# board.net
KiCad netlist of a schematic drawn in EAGLE
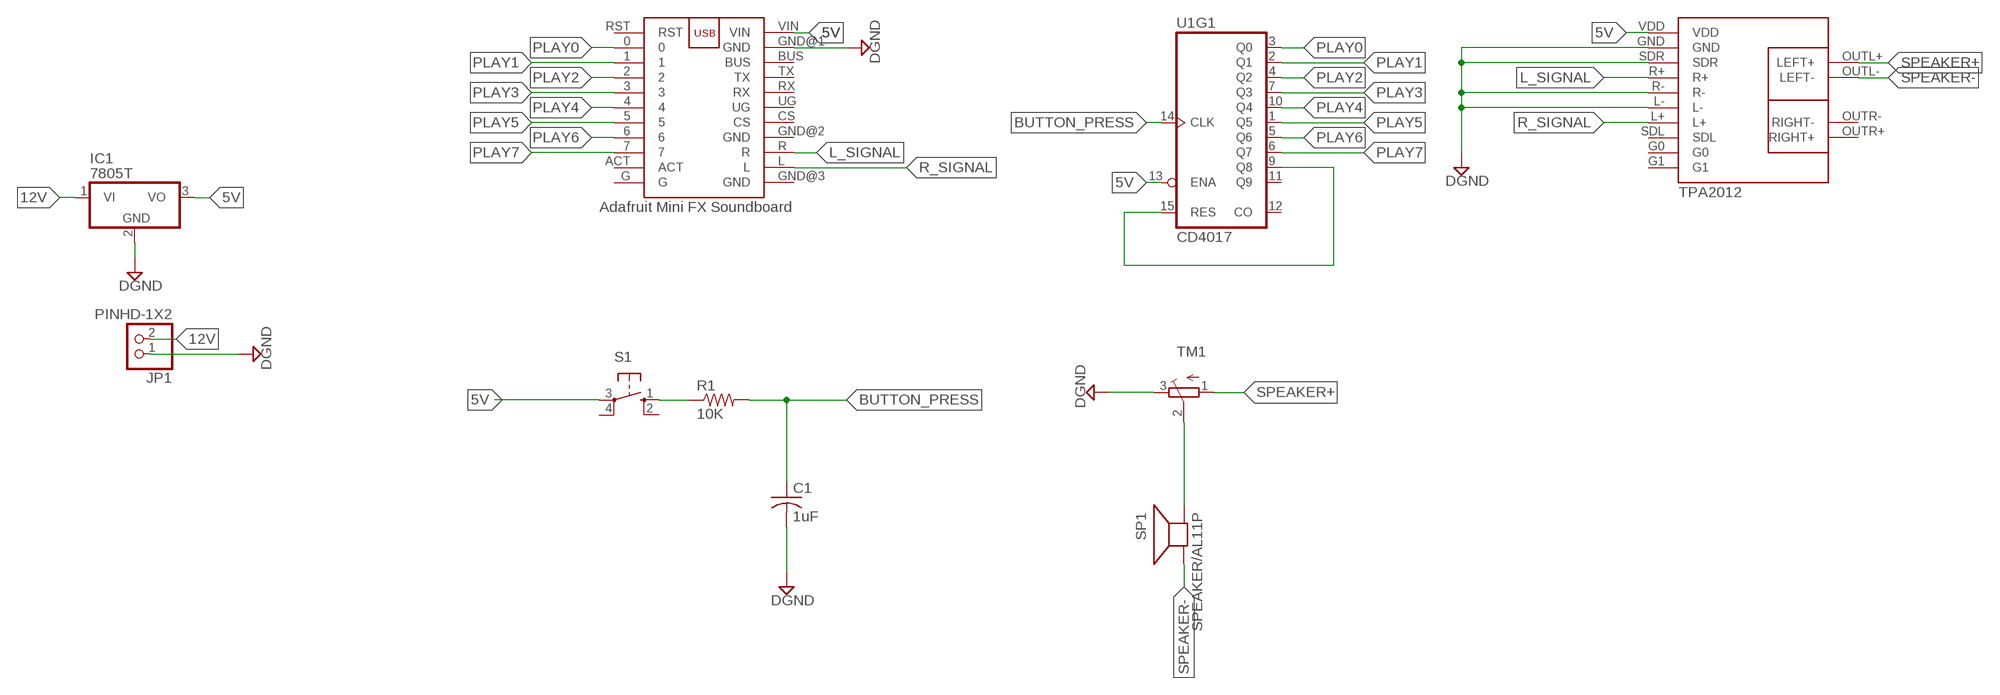
[diagram p0: schematic, sheet 1]

(export (version "E")
  (design (tool "Eeschema 10.0.6"))
  (components
    (comp (ref "C1")
      (value "1uF")
      (footprint "eagle-import:C025-050X050")
      (libsource (lib "eagle-import") (part "C-US025-050X050"))
    )
    (comp (ref "IC1")
      (value "7805T")
      (footprint "eagle-import:TO220H")
      (libsource (lib "eagle-import") (part "78T05"))
    )
    (comp (ref "JP1")
      (value "PINHD-1X2")
      (footprint "eagle-import:1X02")
      (libsource (lib "eagle-import") (part "PINHD-1X2"))
    )
    (comp (ref "R1")
      (value "10K")
      (footprint "eagle-import:0204_5")
      (libsource (lib "eagle-import") (part "R-US_0204/5"))
    )
    (comp (ref "S1")
      (value "10-XX")
      (footprint "eagle-import:B3F-10XX")
      (fields (field (name "MPN") "B3F-1000"))
      (libsource (lib "eagle-import") (part "10-XX"))
    )
    (comp (ref "SP1")
      (value "SPEAKER/AL11P")
      (footprint "eagle-import:AL11P")
      (libsource (lib "eagle-import") (part "SPEAKER/AL11P"))
    )
    (comp (ref "TM1")
      (value "TRIMPOT3386")
      (footprint "eagle-import:TRIM-3386")
      (libsource (lib "eagle-import") (part "TRIMPOT3386"))
    )
    (comp (ref "U$1")
      (value "TPA2012")
      (footprint "eagle-import:TPA2012")
      (libsource (lib "eagle-import") (part "TPA2012"))
    )
    (comp (ref "U$2")
      (value "ADAFRUIT_AUDIO_FX_MINI_SOUNDBOARD")
      (footprint "eagle-import:ADAFRUIT_AUDIO_FX_MINI_SOUNDBOARD")
      (libsource (lib "eagle-import") (part "ADAFRUIT_AUDIO_FX_MINI_SOUNDBOARD"))
    )
    (comp (ref "U1")
      (value "CD4017")
      (footprint "eagle-import:DIP16")
      (libsource (lib "eagle-import") (part "CD4017"))
    )
  )
  (nets
    (net (code "1") (name "5V") (class "Default")
      (node (ref "IC1") (pin "3") (pinfunction "VO_3") (pintype "passive"))
      (node (ref "S1") (pin "3") (pinfunction "P_3") (pintype "passive"))
      (node (ref "U$1") (pin "VDD") (pinfunction "VDD_VDD") (pintype "bidirectional"))
      (node (ref "U$2") (pin "VIN") (pinfunction "VIN_VIN") (pintype "bidirectional"))
      (node (ref "U1") (pin "13") (pinfunction "ENA_13") (pintype "input"))
    )
    (net (code "2") (name "12V") (class "Default")
      (node (ref "IC1") (pin "1") (pinfunction "VI_1") (pintype "input"))
      (node (ref "JP1") (pin "2") (pinfunction "2_2") (pintype "passive"))
    )
    (net (code "3") (name "BUTTON_PRESS") (class "Default")
      (node (ref "C1") (pin "1") (pinfunction "1_1") (pintype "passive"))
      (node (ref "R1") (pin "2") (pinfunction "2_2") (pintype "passive"))
      (node (ref "U1") (pin "14") (pinfunction "CLK_14") (pintype "input"))
    )
    (net (code "4") (name "DGND") (class "Default")
      (node (ref "C1") (pin "2") (pinfunction "2_2") (pintype "passive"))
      (node (ref "IC1") (pin "2") (pinfunction "GND_2") (pintype "passive"))
      (node (ref "JP1") (pin "1") (pinfunction "1_1") (pintype "passive"))
      (node (ref "TM1") (pin "3") (pinfunction "E_3") (pintype "passive"))
      (node (ref "U$1") (pin "GND") (pinfunction "GND_GND") (pintype "bidirectional"))
      (node (ref "U$1") (pin "L-") (pinfunction "L-_L-") (pintype "bidirectional"))
      (node (ref "U$1") (pin "R-") (pinfunction "R-_R-") (pintype "bidirectional"))
      (node (ref "U$1") (pin "SDR") (pinfunction "SDR_SDR") (pintype "bidirectional"))
      (node (ref "U$2") (pin "GND@1") (pinfunction "GND_GND@1") (pintype "bidirectional"))
    )
    (net (code "5") (name "L_SIGNAL") (class "Default")
      (node (ref "U$1") (pin "R+") (pinfunction "R+_R+") (pintype "bidirectional"))
      (node (ref "U$2") (pin "R") (pinfunction "R_R") (pintype "bidirectional"))
    )
    (net (code "6") (name "Net-(S1-S)") (class "Default")
      (node (ref "R1") (pin "1") (pinfunction "1_1") (pintype "passive"))
      (node (ref "S1") (pin "1") (pinfunction "S_1") (pintype "passive"))
    )
    (net (code "7") (name "Net-(TM1-S)") (class "Default")
      (node (ref "SP1") (pin "+") (pinfunction "+_+") (pintype "passive"))
      (node (ref "TM1") (pin "2") (pinfunction "S_2") (pintype "passive"))
    )
    (net (code "8") (name "Net-(U1A-Q8)") (class "Default")
      (node (ref "U1") (pin "15") (pinfunction "RES_15") (pintype "input"))
      (node (ref "U1") (pin "9") (pinfunction "Q8_9") (pintype "output"))
    )
    (net (code "9") (name "PLAY0") (class "Default")
      (node (ref "U$2") (pin "0") (pinfunction "0_0") (pintype "bidirectional"))
      (node (ref "U1") (pin "3") (pinfunction "Q0_3") (pintype "output"))
    )
    (net (code "10") (name "PLAY1") (class "Default")
      (node (ref "U$2") (pin "1") (pinfunction "1_1") (pintype "bidirectional"))
      (node (ref "U1") (pin "2") (pinfunction "Q1_2") (pintype "output"))
    )
    (net (code "11") (name "PLAY2") (class "Default")
      (node (ref "U$2") (pin "2") (pinfunction "2_2") (pintype "bidirectional"))
      (node (ref "U1") (pin "4") (pinfunction "Q2_4") (pintype "output"))
    )
    (net (code "12") (name "PLAY3") (class "Default")
      (node (ref "U$2") (pin "3") (pinfunction "3_3") (pintype "bidirectional"))
      (node (ref "U1") (pin "7") (pinfunction "Q3_7") (pintype "output"))
    )
    (net (code "13") (name "PLAY4") (class "Default")
      (node (ref "U$2") (pin "4") (pinfunction "4_4") (pintype "bidirectional"))
      (node (ref "U1") (pin "10") (pinfunction "Q4_10") (pintype "output"))
    )
    (net (code "14") (name "PLAY5") (class "Default")
      (node (ref "U$2") (pin "5") (pinfunction "5_5") (pintype "bidirectional"))
      (node (ref "U1") (pin "1") (pinfunction "Q5_1") (pintype "output"))
    )
    (net (code "15") (name "PLAY6") (class "Default")
      (node (ref "U$2") (pin "6") (pinfunction "6_6") (pintype "bidirectional"))
      (node (ref "U1") (pin "5") (pinfunction "Q6_5") (pintype "output"))
    )
    (net (code "16") (name "PLAY7") (class "Default")
      (node (ref "U$2") (pin "7") (pinfunction "7_7") (pintype "bidirectional"))
      (node (ref "U1") (pin "6") (pinfunction "Q7_6") (pintype "output"))
    )
    (net (code "17") (name "R_SIGNAL") (class "Default")
      (node (ref "U$1") (pin "L+") (pinfunction "L+_L+") (pintype "bidirectional"))
      (node (ref "U$2") (pin "L") (pinfunction "L_L") (pintype "bidirectional"))
    )
    (net (code "18") (name "SPEAKER+") (class "Default")
      (node (ref "TM1") (pin "1") (pinfunction "A_1") (pintype "passive"))
      (node (ref "U$1") (pin "OUTL+") (pinfunction "LEFT+_OUTL+") (pintype "bidirectional"))
    )
    (net (code "19") (name "SPEAKER-") (class "Default")
      (node (ref "SP1") (pin "-") (pinfunction "-_-") (pintype "passive"))
      (node (ref "U$1") (pin "OUTL-") (pinfunction "LEFT-_OUTL-") (pintype "bidirectional"))
    )
    (net (code "20") (name "unconnected-(S1-P1-Pad4)") (class "Default")
      (node (ref "S1") (pin "4") (pinfunction "P1_4") (pintype "passive"))
    )
    (net (code "21") (name "unconnected-(S1-S1-Pad2)") (class "Default")
      (node (ref "S1") (pin "2") (pinfunction "S1_2") (pintype "passive"))
    )
    (net (code "22") (name "unconnected-(U$1-PadG0)") (class "Default")
      (node (ref "U$1") (pin "G0") (pinfunction "G0_G0") (pintype "bidirectional"))
    )
    (net (code "23") (name "unconnected-(U$1-PadG1)") (class "Default")
      (node (ref "U$1") (pin "G1") (pinfunction "G1_G1") (pintype "bidirectional"))
    )
    (net (code "24") (name "unconnected-(U$1-PadSDL)") (class "Default")
      (node (ref "U$1") (pin "SDL") (pinfunction "SDL_SDL") (pintype "bidirectional"))
    )
    (net (code "25") (name "unconnected-(U$1-RIGHT+-PadOUTR+)") (class "Default")
      (node (ref "U$1") (pin "OUTR+") (pinfunction "RIGHT+_OUTR+") (pintype "bidirectional"))
    )
    (net (code "26") (name "unconnected-(U$1-RIGHT--PadOUTR-)") (class "Default")
      (node (ref "U$1") (pin "OUTR-") (pinfunction "RIGHT-_OUTR-") (pintype "bidirectional"))
    )
    (net (code "27") (name "unconnected-(U$2-GND-PadGND@2)") (class "Default")
      (node (ref "U$2") (pin "GND@2") (pinfunction "GND_GND@2") (pintype "bidirectional"))
    )
    (net (code "28") (name "unconnected-(U$2-GND-PadGND@3)") (class "Default")
      (node (ref "U$2") (pin "GND@3") (pinfunction "GND_GND@3") (pintype "bidirectional"))
    )
    (net (code "29") (name "unconnected-(U$2-PadACT)") (class "Default")
      (node (ref "U$2") (pin "ACT") (pinfunction "ACT_ACT") (pintype "bidirectional"))
    )
    (net (code "30") (name "unconnected-(U$2-PadBUS)") (class "Default")
      (node (ref "U$2") (pin "BUS") (pinfunction "BUS_BUS") (pintype "bidirectional"))
    )
    (net (code "31") (name "unconnected-(U$2-PadCS)") (class "Default")
      (node (ref "U$2") (pin "CS") (pinfunction "CS_CS") (pintype "bidirectional"))
    )
    (net (code "32") (name "unconnected-(U$2-PadG)") (class "Default")
      (node (ref "U$2") (pin "G") (pinfunction "G_G") (pintype "bidirectional"))
    )
    (net (code "33") (name "unconnected-(U$2-PadRST)") (class "Default")
      (node (ref "U$2") (pin "RST") (pinfunction "RST_RST") (pintype "bidirectional"))
    )
    (net (code "34") (name "unconnected-(U$2-PadRX)") (class "Default")
      (node (ref "U$2") (pin "RX") (pinfunction "RX_RX") (pintype "bidirectional"))
    )
    (net (code "35") (name "unconnected-(U$2-PadTX)") (class "Default")
      (node (ref "U$2") (pin "TX") (pinfunction "TX_TX") (pintype "bidirectional"))
    )
    (net (code "36") (name "unconnected-(U$2-PadUG)") (class "Default")
      (node (ref "U$2") (pin "UG") (pinfunction "UG_UG") (pintype "bidirectional"))
    )
    (net (code "37") (name "unconnected-(U1A-CO-Pad12)") (class "Default")
      (node (ref "U1") (pin "12") (pinfunction "CO_12") (pintype "output"))
    )
    (net (code "38") (name "unconnected-(U1A-Q9-Pad11)") (class "Default")
      (node (ref "U1") (pin "11") (pinfunction "Q9_11") (pintype "output"))
    )
  )
)
